# Me-Limit_Switch_v2_0.net
KiCad netlist of a schematic drawn in EAGLE
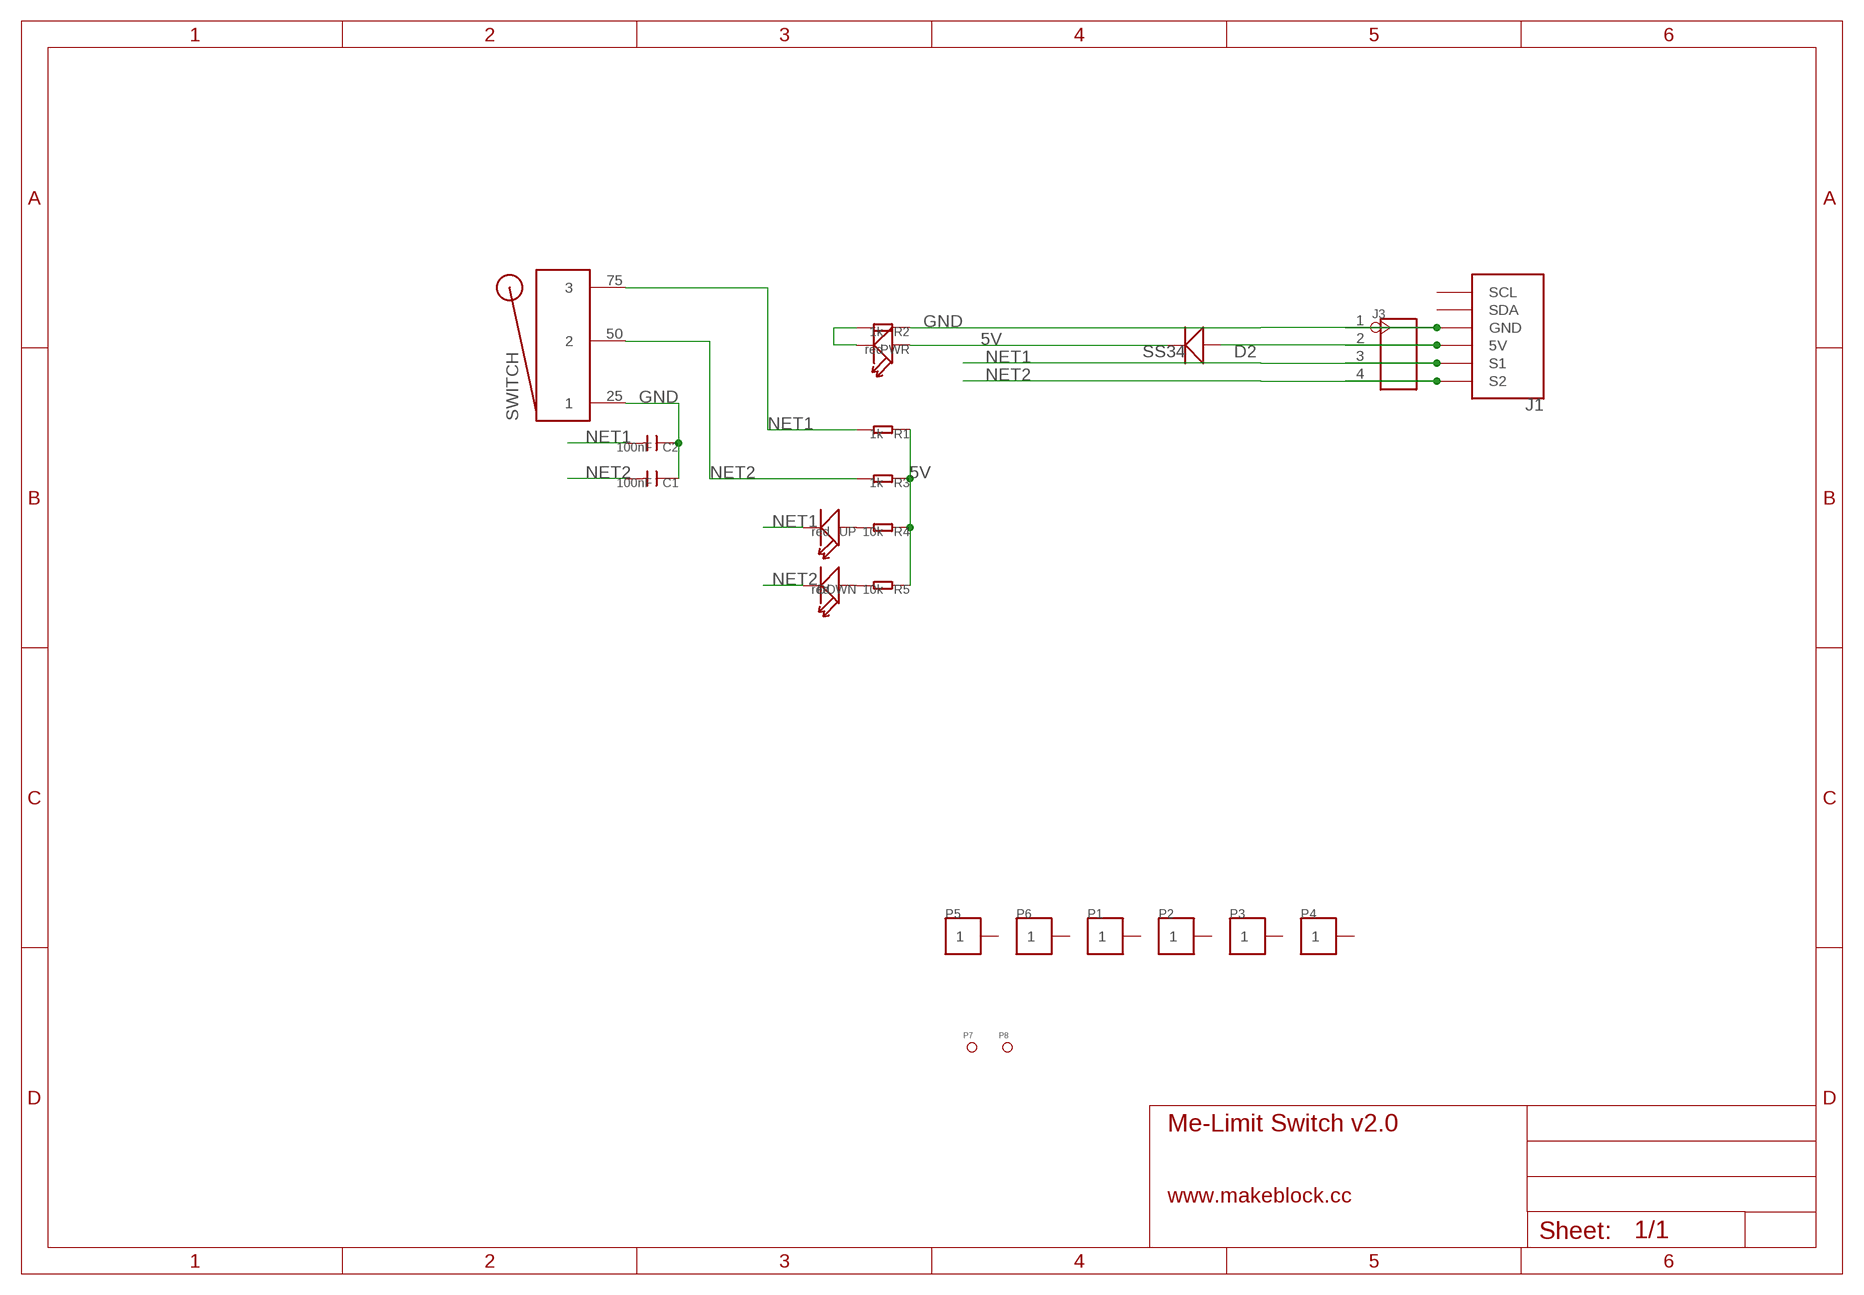
[diagram p0: schematic, sheet 1]

(export (version "E")
  (design (tool "Eeschema 10.0.6"))
  (components
    (comp (ref "C1")
      (value "100nF")
      (footprint "eagle-import:0603")
      (libsource (lib "eagle-import") (part "C-0603"))
    )
    (comp (ref "C2")
      (value "100nF")
      (footprint "eagle-import:0603")
      (libsource (lib "eagle-import") (part "C-0603"))
    )
    (comp (ref "D2")
      (value "SS34")
      (footprint "eagle-import:D2010")
      (libsource (lib "eagle-import") (part "D'SMA'"))
    )
    (comp (ref "DOWN")
      (value "red")
      (footprint "eagle-import:LED-0603")
      (libsource (lib "eagle-import") (part "LED'0603'"))
    )
    (comp (ref "J1")
      (value "RJ11-6P6C-DIGI")
      (footprint "eagle-import:RJ11-6P6C")
      (libsource (lib "eagle-import") (part "RJ11-6P6C-DIGI"))
    )
    (comp (ref "J3")
      (value "HEADER-4P-60/35MIL")
      (footprint "eagle-import:4P-65_35MIL")
      (libsource (lib "eagle-import") (part "HEADER-4P-60/35MIL"))
    )
    (comp (ref "P1")
      (value "PAD-1P-4MM")
      (footprint "eagle-import:HOLE-01")
      (libsource (lib "eagle-import") (part "PAD-1P-4MM"))
    )
    (comp (ref "P2")
      (value "PAD-1P-4MM")
      (footprint "eagle-import:HOLE-01")
      (libsource (lib "eagle-import") (part "PAD-1P-4MM"))
    )
    (comp (ref "P3")
      (value "PAD-1P-4MM")
      (footprint "eagle-import:HOLE-01")
      (libsource (lib "eagle-import") (part "PAD-1P-4MM"))
    )
    (comp (ref "P4")
      (value "PAD-1P-4MM")
      (footprint "eagle-import:HOLE-01")
      (libsource (lib "eagle-import") (part "PAD-1P-4MM"))
    )
    (comp (ref "P5")
      (value "PAD-1P-4MM")
      (footprint "eagle-import:HOLE-01")
      (libsource (lib "eagle-import") (part "PAD-1P-4MM"))
    )
    (comp (ref "P6")
      (value "PAD-1P-4MM")
      (footprint "eagle-import:HOLE-01")
      (libsource (lib "eagle-import") (part "PAD-1P-4MM"))
    )
    (comp (ref "P7")
      (value "PAD-MARK")
      (footprint "eagle-import:ROUND-MARK-1.0")
      (fields (field (name "PARTNO") "DNP"))
      (libsource (lib "eagle-import") (part "PAD-MARK"))
    )
    (comp (ref "P8")
      (value "PAD-MARK")
      (footprint "eagle-import:ROUND-MARK-1.0")
      (fields (field (name "PARTNO") "DNP"))
      (libsource (lib "eagle-import") (part "PAD-MARK"))
    )
    (comp (ref "PWR")
      (value "red")
      (footprint "eagle-import:LED-0603")
      (libsource (lib "eagle-import") (part "LED'0603'"))
    )
    (comp (ref "R1")
      (value "1k")
      (footprint "eagle-import:0603")
      (libsource (lib "eagle-import") (part "R-0603"))
    )
    (comp (ref "R2")
      (value "1k")
      (footprint "eagle-import:0603")
      (libsource (lib "eagle-import") (part "R-0603"))
    )
    (comp (ref "R3")
      (value "1k")
      (footprint "eagle-import:0603")
      (libsource (lib "eagle-import") (part "R-0603"))
    )
    (comp (ref "R4")
      (value "10k")
      (footprint "eagle-import:0603")
      (libsource (lib "eagle-import") (part "R-0603"))
    )
    (comp (ref "R5")
      (value "10k")
      (footprint "eagle-import:0603")
      (libsource (lib "eagle-import") (part "R-0603"))
    )
    (comp (ref "SWITCH")
      (value "OMRON-SS5GL2")
      (footprint "eagle-import:OMRON-SS5GL2")
      (libsource (lib "eagle-import") (part "OMRON-SS5GL2"))
    )
    (comp (ref "UP")
      (value "red")
      (footprint "eagle-import:LED-0603")
      (libsource (lib "eagle-import") (part "LED'0603'"))
    )
  )
  (nets
    (net (code "1") (name "/5V") (class "Default")
      (node (ref "D2") (pin "-") (pinfunction "-_-") (pintype "passive"))
      (node (ref "PWR") (pin "+") (pinfunction "+_+") (pintype "passive"))
      (node (ref "R1") (pin "1") (pinfunction "1_1") (pintype "passive"))
      (node (ref "R3") (pin "1") (pinfunction "1_1") (pintype "passive"))
      (node (ref "R4") (pin "1") (pinfunction "1_1") (pintype "passive"))
      (node (ref "R5") (pin "1") (pinfunction "1_1") (pintype "passive"))
    )
    (net (code "2") (name "/GND") (class "Default")
      (node (ref "C1") (pin "1") (pinfunction "1_1") (pintype "passive"))
      (node (ref "C2") (pin "1") (pinfunction "1_1") (pintype "passive"))
      (node (ref "J1") (pin "3") (pinfunction "GND_3") (pintype "bidirectional"))
      (node (ref "J3") (pin "1") (pinfunction "P$1_1") (pintype "bidirectional"))
      (node (ref "R2") (pin "1") (pinfunction "1_1") (pintype "passive"))
      (node (ref "SWITCH") (pin "25") (pinfunction "1_25") (pintype "bidirectional"))
    )
    (net (code "3") (name "/NET1") (class "Default")
      (node (ref "C2") (pin "2") (pinfunction "2_2") (pintype "passive"))
      (node (ref "J1") (pin "5") (pinfunction "S1_5") (pintype "bidirectional"))
      (node (ref "J3") (pin "3") (pinfunction "P$3_3") (pintype "bidirectional"))
      (node (ref "R1") (pin "2") (pinfunction "2_2") (pintype "passive"))
      (node (ref "SWITCH") (pin "75") (pinfunction "3_75") (pintype "bidirectional"))
      (node (ref "UP") (pin "-") (pinfunction "-_-") (pintype "passive"))
    )
    (net (code "4") (name "/NET2") (class "Default")
      (node (ref "C1") (pin "2") (pinfunction "2_2") (pintype "passive"))
      (node (ref "DOWN") (pin "-") (pinfunction "-_-") (pintype "passive"))
      (node (ref "J1") (pin "6") (pinfunction "S2_6") (pintype "bidirectional"))
      (node (ref "J3") (pin "4") (pinfunction "P$4_4") (pintype "bidirectional"))
      (node (ref "R3") (pin "2") (pinfunction "2_2") (pintype "passive"))
      (node (ref "SWITCH") (pin "50") (pinfunction "2_50") (pintype "bidirectional"))
    )
    (net (code "5") (name "Net-(DOWN-Pad+)") (class "Default")
      (node (ref "DOWN") (pin "+") (pinfunction "+_+") (pintype "passive"))
      (node (ref "R5") (pin "2") (pinfunction "2_2") (pintype "passive"))
    )
    (net (code "6") (name "Net-(J1-5V)") (class "Default")
      (node (ref "D2") (pin "+") (pinfunction "+_+") (pintype "passive"))
      (node (ref "J1") (pin "4") (pinfunction "5V_4") (pintype "bidirectional"))
      (node (ref "J3") (pin "2") (pinfunction "P$2_2") (pintype "bidirectional"))
    )
    (net (code "7") (name "Net-(PWR-Pad-)") (class "Default")
      (node (ref "PWR") (pin "-") (pinfunction "-_-") (pintype "passive"))
      (node (ref "R2") (pin "2") (pinfunction "2_2") (pintype "passive"))
    )
    (net (code "8") (name "Net-(R4-Pad2)") (class "Default")
      (node (ref "R4") (pin "2") (pinfunction "2_2") (pintype "passive"))
      (node (ref "UP") (pin "+") (pinfunction "+_+") (pintype "passive"))
    )
    (net (code "9") (name "unconnected-(J1-SCL-Pad1)") (class "Default")
      (node (ref "J1") (pin "1") (pinfunction "SCL_1") (pintype "bidirectional"))
    )
    (net (code "10") (name "unconnected-(J1-SDA-Pad2)") (class "Default")
      (node (ref "J1") (pin "2") (pinfunction "SDA_2") (pintype "bidirectional"))
    )
    (net (code "11") (name "unconnected-(P1-Pad1)") (class "Default")
      (node (ref "P1") (pin "1") (pinfunction "1_1") (pintype "bidirectional"))
    )
    (net (code "12") (name "unconnected-(P2-Pad1)") (class "Default")
      (node (ref "P2") (pin "1") (pinfunction "1_1") (pintype "bidirectional"))
    )
    (net (code "13") (name "unconnected-(P3-Pad1)") (class "Default")
      (node (ref "P3") (pin "1") (pinfunction "1_1") (pintype "bidirectional"))
    )
    (net (code "14") (name "unconnected-(P4-Pad1)") (class "Default")
      (node (ref "P4") (pin "1") (pinfunction "1_1") (pintype "bidirectional"))
    )
    (net (code "15") (name "unconnected-(P5-Pad1)") (class "Default")
      (node (ref "P5") (pin "1") (pinfunction "1_1") (pintype "bidirectional"))
    )
    (net (code "16") (name "unconnected-(P6-Pad1)") (class "Default")
      (node (ref "P6") (pin "1") (pinfunction "1_1") (pintype "bidirectional"))
    )
  )
)
